# 4_Vibrationdriver_MSP430.net
KiCad netlist of a schematic drawn in EAGLE
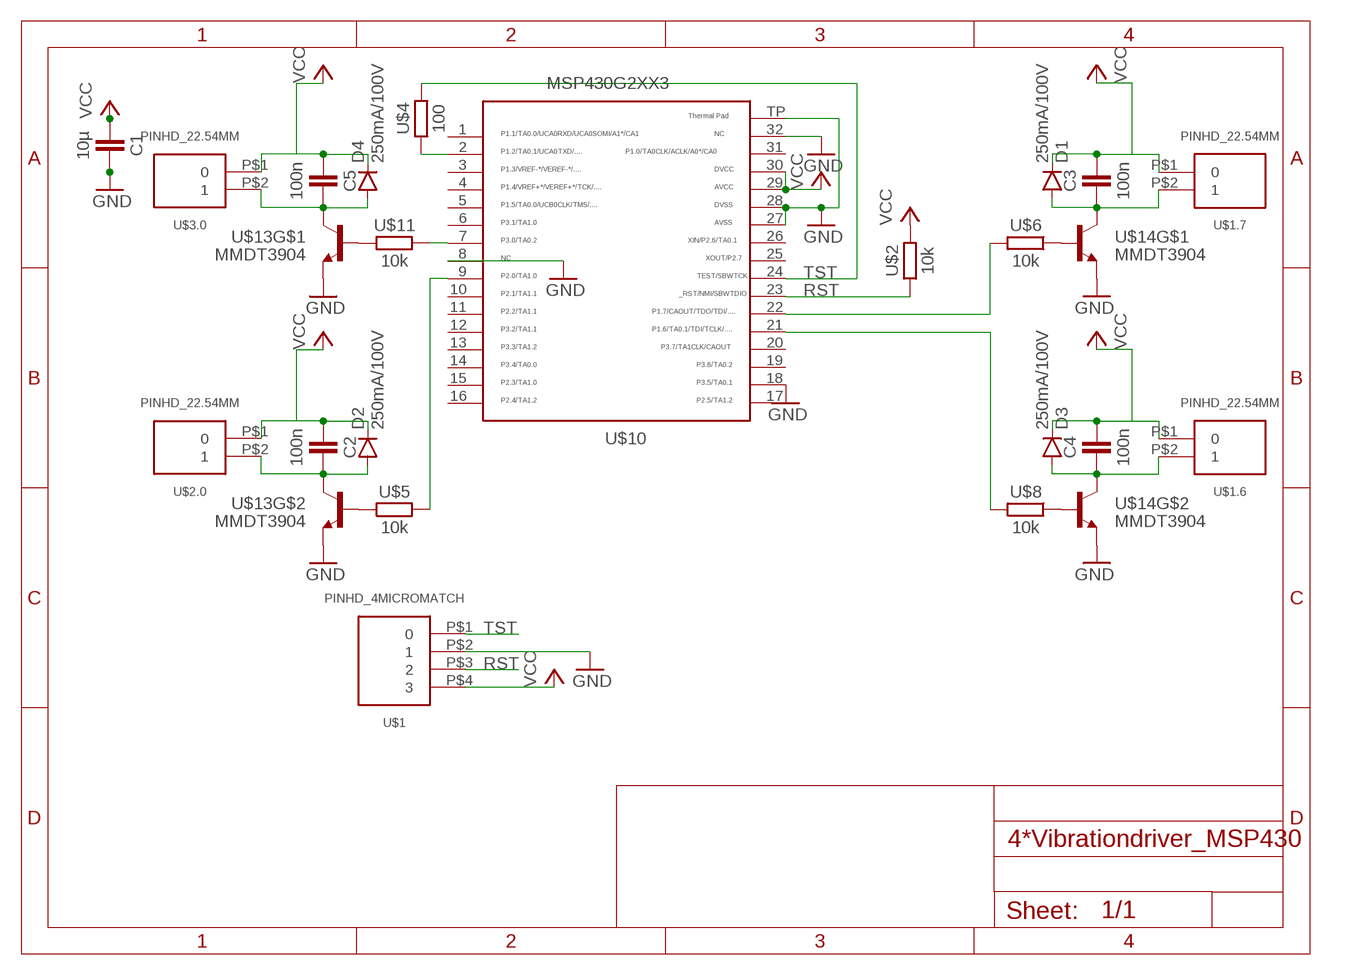
[diagram p0: schematic, sheet 1]

(export (version "E")
  (design (tool "Eeschema 10.0.6"))
  (components
    (comp (ref "C1")
      (value "10µ")
      (footprint "eagle-import:603")
      (libsource (lib "eagle-import") (part "CAPACITOR"))
    )
    (comp (ref "C2")
      (value "100n")
      (footprint "eagle-import:603")
      (libsource (lib "eagle-import") (part "CAPACITOR"))
    )
    (comp (ref "C3")
      (value "100n")
      (footprint "eagle-import:603")
      (libsource (lib "eagle-import") (part "CAPACITOR"))
    )
    (comp (ref "C4")
      (value "100n")
      (footprint "eagle-import:603")
      (libsource (lib "eagle-import") (part "CAPACITOR"))
    )
    (comp (ref "C5")
      (value "100n")
      (footprint "eagle-import:603")
      (libsource (lib "eagle-import") (part "CAPACITOR"))
    )
    (comp (ref "D1")
      (value "250mA/100V")
      (footprint "eagle-import:SOD-323")
      (libsource (lib "eagle-import") (part "DIODEBAS16"))
    )
    (comp (ref "D2")
      (value "250mA/100V")
      (footprint "eagle-import:SOD-323")
      (libsource (lib "eagle-import") (part "DIODEBAS16"))
    )
    (comp (ref "D3")
      (value "250mA/100V")
      (footprint "eagle-import:SOD-323")
      (libsource (lib "eagle-import") (part "DIODEBAS16"))
    )
    (comp (ref "D4")
      (value "250mA/100V")
      (footprint "eagle-import:SOD-323")
      (libsource (lib "eagle-import") (part "DIODEBAS16"))
    )
    (comp (ref "U$1")
      (value "PINHD_4MICROMATCH")
      (footprint "eagle-import:MICROMATCH4P0L")
      (libsource (lib "eagle-import") (part "PINHD_4MICROMATCH"))
    )
    (comp (ref "U$1.6")
      (value "PINHD_22.54MM")
      (footprint "eagle-import:PINHD2")
      (libsource (lib "eagle-import") (part "PINHD_22.54MM"))
    )
    (comp (ref "U$1.7")
      (value "PINHD_22.54MM")
      (footprint "eagle-import:PINHD2")
      (libsource (lib "eagle-import") (part "PINHD_22.54MM"))
    )
    (comp (ref "U$2")
      (value "10k")
      (footprint "eagle-import:603")
      (libsource (lib "eagle-import") (part "RESISTOR0603"))
    )
    (comp (ref "U$2.0")
      (value "PINHD_22.54MM")
      (footprint "eagle-import:PINHD2")
      (libsource (lib "eagle-import") (part "PINHD_22.54MM"))
    )
    (comp (ref "U$3.0")
      (value "PINHD_22.54MM")
      (footprint "eagle-import:PINHD2")
      (libsource (lib "eagle-import") (part "PINHD_22.54MM"))
    )
    (comp (ref "U$4")
      (value "100")
      (footprint "eagle-import:603")
      (libsource (lib "eagle-import") (part "RESISTOR0603"))
    )
    (comp (ref "U$5")
      (value "10k")
      (footprint "eagle-import:603")
      (libsource (lib "eagle-import") (part "RESISTOR0603"))
    )
    (comp (ref "U$6")
      (value "10k")
      (footprint "eagle-import:603")
      (libsource (lib "eagle-import") (part "RESISTOR0603"))
    )
    (comp (ref "U$8")
      (value "10k")
      (footprint "eagle-import:603")
      (libsource (lib "eagle-import") (part "RESISTOR0603"))
    )
    (comp (ref "U$10")
      (value "MSP430G2553")
      (footprint "eagle-import:QFN32")
      (libsource (lib "eagle-import") (part "MSP430G2553"))
    )
    (comp (ref "U$11")
      (value "10k")
      (footprint "eagle-import:603")
      (libsource (lib "eagle-import") (part "RESISTOR0603"))
    )
    (comp (ref "U$13")
      (value "MMDT3904")
      (footprint "eagle-import:SOT363")
      (libsource (lib "eagle-import") (part "TRANSISTOR_NPN2UPMMDT3904"))
    )
    (comp (ref "U$14")
      (value "MMDT3904")
      (footprint "eagle-import:SOT363")
      (libsource (lib "eagle-import") (part "TRANSISTOR_NPN2UPMMDT3904"))
    )
  )
  (nets
    (net (code "1") (name "/RST") (class "Default")
      (node (ref "U$1") (pin "P$3") (pinfunction "2_P$3") (pintype "bidirectional"))
      (node (ref "U$10") (pin "23") (pinfunction "23_23") (pintype "bidirectional"))
      (node (ref "U$2") (pin "1") (pinfunction "1_1") (pintype "passive"))
    )
    (net (code "2") (name "/TST") (class "Default")
      (node (ref "U$1") (pin "P$1") (pinfunction "0_P$1") (pintype "bidirectional"))
      (node (ref "U$10") (pin "24") (pinfunction "24_24") (pintype "bidirectional"))
      (node (ref "U$4") (pin "2") (pinfunction "2_2") (pintype "passive"))
    )
    (net (code "3") (name "GND") (class "Default")
      (node (ref "C1") (pin "2") (pinfunction "2_2") (pintype "passive"))
      (node (ref "U$1") (pin "P$2") (pinfunction "1_P$2") (pintype "bidirectional"))
      (node (ref "U$10") (pin "18") (pinfunction "18_18") (pintype "bidirectional"))
      (node (ref "U$10") (pin "27") (pinfunction "27_27") (pintype "bidirectional"))
      (node (ref "U$10") (pin "28") (pinfunction "28_28") (pintype "bidirectional"))
      (node (ref "U$10") (pin "32") (pinfunction "32_32") (pintype "bidirectional"))
      (node (ref "U$10") (pin "8") (pinfunction "8_8") (pintype "bidirectional"))
      (node (ref "U$10") (pin "TP") (pinfunction "TP_TP") (pintype "bidirectional"))
      (node (ref "U$13") (pin "1") (pinfunction "E_1") (pintype "passive"))
      (node (ref "U$13") (pin "4") (pinfunction "E_4") (pintype "passive"))
      (node (ref "U$14") (pin "1") (pinfunction "E_1") (pintype "passive"))
      (node (ref "U$14") (pin "4") (pinfunction "E_4") (pintype "passive"))
    )
    (net (code "4") (name "Net-(U$1.6-1)") (class "Default")
      (node (ref "C4") (pin "2") (pinfunction "2_2") (pintype "passive"))
      (node (ref "D3") (pin "A") (pinfunction "A_A") (pintype "passive"))
      (node (ref "U$1.6") (pin "P$2") (pinfunction "1_P$2") (pintype "bidirectional"))
      (node (ref "U$14") (pin "3") (pinfunction "C_3") (pintype "passive"))
    )
    (net (code "5") (name "Net-(U$1.7-1)") (class "Default")
      (node (ref "C3") (pin "2") (pinfunction "2_2") (pintype "passive"))
      (node (ref "D1") (pin "A") (pinfunction "A_A") (pintype "passive"))
      (node (ref "U$1.7") (pin "P$2") (pinfunction "1_P$2") (pintype "bidirectional"))
      (node (ref "U$14") (pin "6") (pinfunction "C_6") (pintype "passive"))
    )
    (net (code "6") (name "Net-(U$10-Pad2)") (class "Default")
      (node (ref "U$10") (pin "2") (pinfunction "2_2") (pintype "bidirectional"))
      (node (ref "U$4") (pin "1") (pinfunction "1_1") (pintype "passive"))
    )
    (net (code "7") (name "Net-(U$10-Pad7)") (class "Default")
      (node (ref "U$10") (pin "7") (pinfunction "7_7") (pintype "bidirectional"))
      (node (ref "U$11") (pin "2") (pinfunction "2_2") (pintype "passive"))
    )
    (net (code "8") (name "Net-(U$10-Pad9)") (class "Default")
      (node (ref "U$10") (pin "9") (pinfunction "9_9") (pintype "bidirectional"))
      (node (ref "U$5") (pin "2") (pinfunction "2_2") (pintype "passive"))
    )
    (net (code "9") (name "Net-(U$10-Pad21)") (class "Default")
      (node (ref "U$10") (pin "21") (pinfunction "21_21") (pintype "bidirectional"))
      (node (ref "U$8") (pin "2") (pinfunction "2_2") (pintype "passive"))
    )
    (net (code "10") (name "Net-(U$10-Pad22)") (class "Default")
      (node (ref "U$10") (pin "22") (pinfunction "22_22") (pintype "bidirectional"))
      (node (ref "U$6") (pin "2") (pinfunction "2_2") (pintype "passive"))
    )
    (net (code "11") (name "Net-(U$13A-B)") (class "Default")
      (node (ref "U$11") (pin "1") (pinfunction "1_1") (pintype "passive"))
      (node (ref "U$13") (pin "2") (pinfunction "B_2") (pintype "passive"))
    )
    (net (code "12") (name "Net-(U$13A-C)") (class "Default")
      (node (ref "C5") (pin "2") (pinfunction "2_2") (pintype "passive"))
      (node (ref "D4") (pin "A") (pinfunction "A_A") (pintype "passive"))
      (node (ref "U$13") (pin "6") (pinfunction "C_6") (pintype "passive"))
      (node (ref "U$3.0") (pin "P$2") (pinfunction "1_P$2") (pintype "bidirectional"))
    )
    (net (code "13") (name "Net-(U$13B-B)") (class "Default")
      (node (ref "U$13") (pin "5") (pinfunction "B_5") (pintype "passive"))
      (node (ref "U$5") (pin "1") (pinfunction "1_1") (pintype "passive"))
    )
    (net (code "14") (name "Net-(U$13B-C)") (class "Default")
      (node (ref "C2") (pin "2") (pinfunction "2_2") (pintype "passive"))
      (node (ref "D2") (pin "A") (pinfunction "A_A") (pintype "passive"))
      (node (ref "U$13") (pin "3") (pinfunction "C_3") (pintype "passive"))
      (node (ref "U$2.0") (pin "P$2") (pinfunction "1_P$2") (pintype "bidirectional"))
    )
    (net (code "15") (name "Net-(U$14A-B)") (class "Default")
      (node (ref "U$14") (pin "2") (pinfunction "B_2") (pintype "passive"))
      (node (ref "U$6") (pin "1") (pinfunction "1_1") (pintype "passive"))
    )
    (net (code "16") (name "Net-(U$14B-B)") (class "Default")
      (node (ref "U$14") (pin "5") (pinfunction "B_5") (pintype "passive"))
      (node (ref "U$8") (pin "1") (pinfunction "1_1") (pintype "passive"))
    )
    (net (code "17") (name "VCC") (class "Default")
      (node (ref "C1") (pin "1") (pinfunction "1_1") (pintype "passive"))
      (node (ref "C2") (pin "1") (pinfunction "1_1") (pintype "passive"))
      (node (ref "C3") (pin "1") (pinfunction "1_1") (pintype "passive"))
      (node (ref "C4") (pin "1") (pinfunction "1_1") (pintype "passive"))
      (node (ref "C5") (pin "1") (pinfunction "1_1") (pintype "passive"))
      (node (ref "D1") (pin "C") (pinfunction "C_C") (pintype "passive"))
      (node (ref "D2") (pin "C") (pinfunction "C_C") (pintype "passive"))
      (node (ref "D3") (pin "C") (pinfunction "C_C") (pintype "passive"))
      (node (ref "D4") (pin "C") (pinfunction "C_C") (pintype "passive"))
      (node (ref "U$1") (pin "P$4") (pinfunction "3_P$4") (pintype "bidirectional"))
      (node (ref "U$1.6") (pin "P$1") (pinfunction "0_P$1") (pintype "bidirectional"))
      (node (ref "U$1.7") (pin "P$1") (pinfunction "0_P$1") (pintype "bidirectional"))
      (node (ref "U$10") (pin "29") (pinfunction "29_29") (pintype "bidirectional"))
      (node (ref "U$10") (pin "30") (pinfunction "30_30") (pintype "bidirectional"))
      (node (ref "U$2") (pin "2") (pinfunction "2_2") (pintype "passive"))
      (node (ref "U$2.0") (pin "P$1") (pinfunction "0_P$1") (pintype "bidirectional"))
      (node (ref "U$3.0") (pin "P$1") (pinfunction "0_P$1") (pintype "bidirectional"))
    )
    (net (code "18") (name "unconnected-(U$10-Pad1)") (class "Default")
      (node (ref "U$10") (pin "1") (pinfunction "1_1") (pintype "bidirectional"))
    )
    (net (code "19") (name "unconnected-(U$10-Pad3)") (class "Default")
      (node (ref "U$10") (pin "3") (pinfunction "3_3") (pintype "bidirectional"))
    )
    (net (code "20") (name "unconnected-(U$10-Pad4)") (class "Default")
      (node (ref "U$10") (pin "4") (pinfunction "4_4") (pintype "bidirectional"))
    )
    (net (code "21") (name "unconnected-(U$10-Pad5)") (class "Default")
      (node (ref "U$10") (pin "5") (pinfunction "5_5") (pintype "bidirectional"))
    )
    (net (code "22") (name "unconnected-(U$10-Pad6)") (class "Default")
      (node (ref "U$10") (pin "6") (pinfunction "6_6") (pintype "bidirectional"))
    )
    (net (code "23") (name "unconnected-(U$10-Pad10)") (class "Default")
      (node (ref "U$10") (pin "10") (pinfunction "10_10") (pintype "bidirectional"))
    )
    (net (code "24") (name "unconnected-(U$10-Pad11)") (class "Default")
      (node (ref "U$10") (pin "11") (pinfunction "11_11") (pintype "bidirectional"))
    )
    (net (code "25") (name "unconnected-(U$10-Pad12)") (class "Default")
      (node (ref "U$10") (pin "12") (pinfunction "12_12") (pintype "bidirectional"))
    )
    (net (code "26") (name "unconnected-(U$10-Pad13)") (class "Default")
      (node (ref "U$10") (pin "13") (pinfunction "13_13") (pintype "bidirectional"))
    )
    (net (code "27") (name "unconnected-(U$10-Pad14)") (class "Default")
      (node (ref "U$10") (pin "14") (pinfunction "14_14") (pintype "bidirectional"))
    )
    (net (code "28") (name "unconnected-(U$10-Pad15)") (class "Default")
      (node (ref "U$10") (pin "15") (pinfunction "15_15") (pintype "bidirectional"))
    )
    (net (code "29") (name "unconnected-(U$10-Pad16)") (class "Default")
      (node (ref "U$10") (pin "16") (pinfunction "16_16") (pintype "bidirectional"))
    )
    (net (code "30") (name "unconnected-(U$10-Pad17)") (class "Default")
      (node (ref "U$10") (pin "17") (pinfunction "17_17") (pintype "bidirectional"))
    )
    (net (code "31") (name "unconnected-(U$10-Pad19)") (class "Default")
      (node (ref "U$10") (pin "19") (pinfunction "19_19") (pintype "bidirectional"))
    )
    (net (code "32") (name "unconnected-(U$10-Pad20)") (class "Default")
      (node (ref "U$10") (pin "20") (pinfunction "20_20") (pintype "bidirectional"))
    )
    (net (code "33") (name "unconnected-(U$10-Pad25)") (class "Default")
      (node (ref "U$10") (pin "25") (pinfunction "25_25") (pintype "bidirectional"))
    )
    (net (code "34") (name "unconnected-(U$10-Pad26)") (class "Default")
      (node (ref "U$10") (pin "26") (pinfunction "26_26") (pintype "bidirectional"))
    )
    (net (code "35") (name "unconnected-(U$10-Pad31)") (class "Default")
      (node (ref "U$10") (pin "31") (pinfunction "31_31") (pintype "bidirectional"))
    )
  )
)
